# charger.net
KiCad netlist of a schematic drawn in Altium Designer
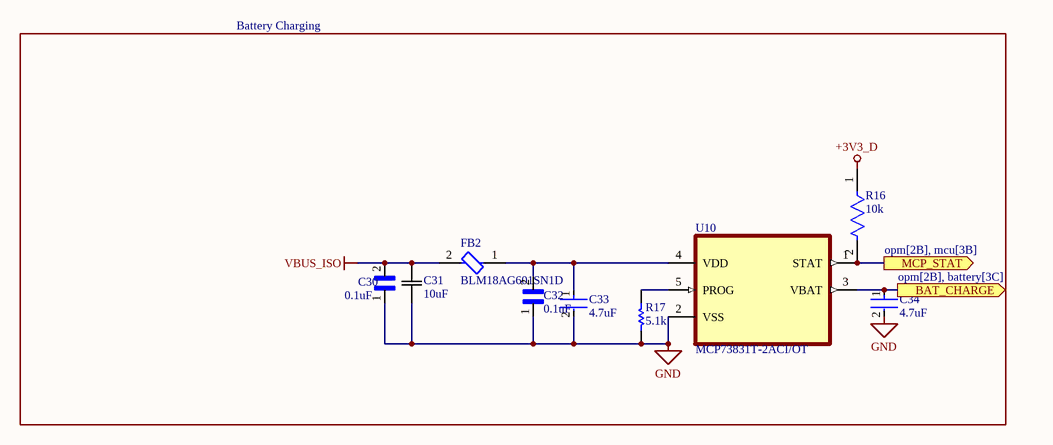
[diagram p0: charger.SchDoc]

(export (version "E")
  (design (tool "Eeschema 10.0.6"))
  (components
    (comp (ref "C30")
      (value "0.1uF")
      (footprint "CC0603JRX7R8BB104")
      (description "25V 100nF X7R ±5% 0603 Multilayer Ceramic Capacitors MLCC - SMD/SMT ROHS")
      (fields
        (field (name "MANUFACTURER") "Yageo Group")
        (field (name "MANUFACTURER PART NUMBER") "CC0603JRX7R8BB104")
      )
      (libsource (lib "opm_lib") (part "CC0603JRX7R8BB104"))
    )
    (comp (ref "C31")
      (value "10uF")
      (footprint "CC0805KKX7R7BB106")
      (description "16V 10uF X7R ±10% 0805 Multilayer Ceramic Capacitors MLCC - SMD/SMT ROHS")
      (fields
        (field (name "MANUFACTURER") "Yageo Group")
        (field (name "MANUFACTURER PART NUMBER") "CC0805KKX7R7BB106")
      )
      (libsource (lib "opm_lib") (part "CC0805KKX7R7BB106"))
    )
    (comp (ref "C32")
      (value "0.1uF")
      (footprint "CC0603JRX7R8BB104")
      (description "25V 100nF X7R ±5% 0603 Multilayer Ceramic Capacitors MLCC - SMD/SMT ROHS")
      (fields
        (field (name "MANUFACTURER") "Yageo Group")
        (field (name "MANUFACTURER PART NUMBER") "CC0603JRX7R8BB104")
      )
      (libsource (lib "opm_lib") (part "CC0603JRX7R8BB104"))
    )
    (comp (ref "C33")
      (value "4.7uF")
      (footprint "CC0805KKX7R7BB106")
      (description "16V 4.7uF X7R ±10% 0805 Multilayer Ceramic Capacitors MLCC - SMD/SMT ROHS")
      (fields
        (field (name "MANUFACTURER") "Yageo Group")
        (field (name "MANUFACTURER PART NUMBER") "CC0805KKX7R7BB475")
      )
      (libsource (lib "opm_lib") (part "CC0805KKX7R7BB475"))
    )
    (comp (ref "C34")
      (value "4.7uF")
      (footprint "CC0805KKX7R7BB106")
      (description "16V 4.7uF X7R ±10% 0805 Multilayer Ceramic Capacitors MLCC - SMD/SMT ROHS")
      (fields
        (field (name "MANUFACTURER") "Yageo Group")
        (field (name "MANUFACTURER PART NUMBER") "CC0805KKX7R7BB475")
      )
      (libsource (lib "opm_lib") (part "CC0805KKX7R7BB475"))
    )
    (comp (ref "FB2")
      (value "BLM18AG601SN1D")
      (footprint "BLM18AG601SN1D")
      (description "Ferrite Beads Multi-Layer 600Ohm 25% 100MHz 500mA 380mOhm DCR 0603 Automotive Paper T/R")
      (fields (field (name "MANUFACTURER") "Murata") (field (name "TOLERANCE") "25%"))
      (libsource (lib "opm_lib") (part "BLM18AG601SN1D"))
    )
    (comp (ref "R16")
      (value "10k")
      (footprint "RC0603FR-07")
      (description "100mW Thick Film Resistors 75V ±100ppm/℃ ±1% 10kΩ 0603 Chip Resistor - Surface Mount ROHS")
      (fields
        (field (name "MANUFACTURER") "Yageo Group")
        (field (name "MANUFACTURER PART NUMBER") "RC0603FR-0710KL")
      )
      (libsource (lib "opm_lib") (part "RC0603FR-0710KL"))
    )
    (comp (ref "R17")
      (value "5.1k")
      (footprint "RC0603FR-07")
      (description "Res Thick Film 0603 5.1K Ohm 1% 0.1W(1/10W) ±100ppm/C Pad SMD T/R")
      (fields
        (field (name "MANUFACTURER") "Yageo Group")
        (field (name "MANUFACTURER PART NUMBER") "RC0603FR-075K1L")
      )
      (libsource (lib "opm_lib") (part "RC0603FR-075K1L"))
    )
    (comp (ref "U10")
      (value "MCP73831T-2ACI/OT")
      (footprint "SOT95P280X145-5N")
      (description "MCP73831 Series Single-Cell Li-Ion/Li-Polymer Battery Charge Controller SOT-23-5")
      (fields (field (name "MANUFACTURER") "Microchip"))
      (libsource (lib "opm_lib") (part "MCP73831T-2ACI/OT"))
    )
  )
  (nets
    (net (code "1") (name "+3V3_D") (class "Default")
      (node (ref "R16") (pin "1") (pinfunction "1_1") (pintype "passive"))
    )
    (net (code "2") (name "/BAT_CHARGE") (class "Default")
      (node (ref "C34") (pin "1") (pinfunction "1_1") (pintype "passive"))
      (node (ref "U10") (pin "3") (pinfunction "VBAT_3") (pintype "output"))
    )
    (net (code "3") (name "/MCP_STAT") (class "Default")
      (node (ref "R16") (pin "2") (pinfunction "2_2") (pintype "passive"))
      (node (ref "U10") (pin "1") (pinfunction "STAT_1") (pintype "output"))
    )
    (net (code "4") (name "GND") (class "Default")
      (node (ref "C30") (pin "1") (pinfunction "1_1") (pintype "passive"))
      (node (ref "C31") (pin "2") (pinfunction "2_2") (pintype "passive"))
      (node (ref "C32") (pin "1") (pinfunction "1_1") (pintype "passive"))
      (node (ref "C33") (pin "2") (pinfunction "2_2") (pintype "passive"))
      (node (ref "C34") (pin "2") (pinfunction "2_2") (pintype "passive"))
      (node (ref "R17") (pin "1") (pinfunction "1_1") (pintype "passive"))
      (node (ref "U10") (pin "2") (pinfunction "VSS_2") (pintype "power_in"))
    )
    (net (code "5") (name "Net-(U10-PROG)") (class "Default")
      (node (ref "R17") (pin "2") (pinfunction "2_2") (pintype "passive"))
      (node (ref "U10") (pin "5") (pinfunction "PROG_5") (pintype "input"))
    )
    (net (code "6") (name "Net-(U10-VDD)") (class "Default")
      (node (ref "C32") (pin "2") (pinfunction "2_2") (pintype "passive"))
      (node (ref "C33") (pin "1") (pinfunction "1_1") (pintype "passive"))
      (node (ref "FB2") (pin "1") (pinfunction "1_1") (pintype "passive"))
      (node (ref "U10") (pin "4") (pinfunction "VDD_4") (pintype "power_in"))
    )
    (net (code "7") (name "VBUS_ISO") (class "Default")
      (node (ref "C30") (pin "2") (pinfunction "2_2") (pintype "passive"))
      (node (ref "C31") (pin "1") (pinfunction "1_1") (pintype "passive"))
      (node (ref "FB2") (pin "2") (pinfunction "2_2") (pintype "passive"))
    )
  )
)
